# FlyballETS-PWR.net
KiCad netlist of a schematic drawn in EAGLE
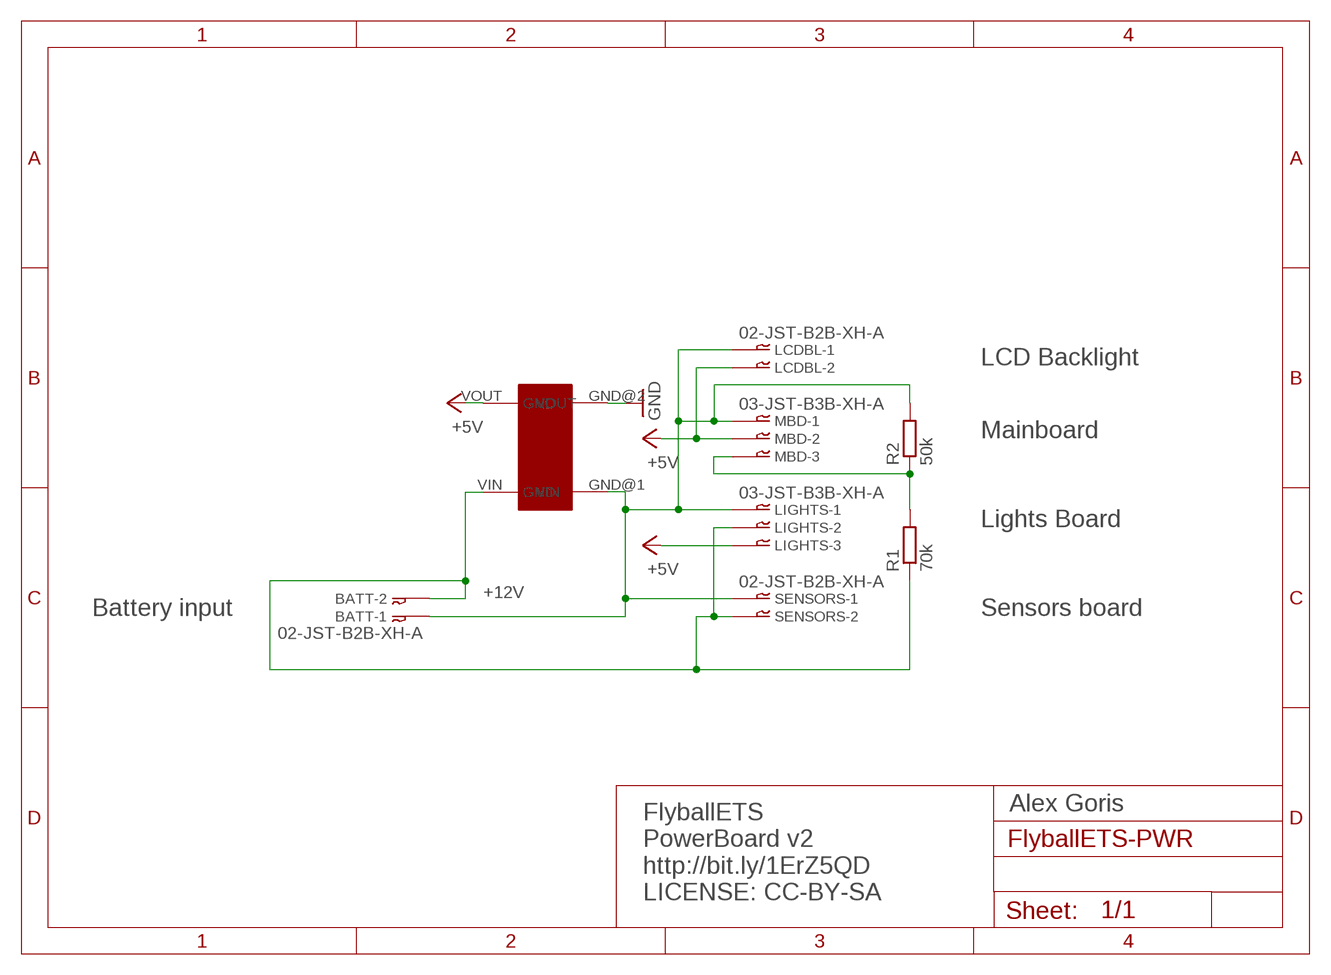
[diagram p0: schematic, sheet 1]

(export (version "E")
  (design (tool "Eeschema 10.0.6"))
  (components
    (comp (ref "BATT")
      (value "02-JST-B2B-XH-A")
      (footprint "eagle-import:B2B-XH")
      (libsource (lib "eagle-import") (part "02-JST-B2B-XH-A"))
    )
    (comp (ref "LCDBL")
      (value "02-JST-B2B-XH-A")
      (footprint "eagle-import:B2B-XH")
      (libsource (lib "eagle-import") (part "02-JST-B2B-XH-A"))
    )
    (comp (ref "LIGHTS")
      (value "03-JST-B3B-XH-A")
      (footprint "eagle-import:B3B-XH")
      (libsource (lib "eagle-import") (part "03-JST-B3B-XH-A"))
    )
    (comp (ref "MBD")
      (value "03-JST-B3B-XH-A")
      (footprint "eagle-import:B3B-XH")
      (libsource (lib "eagle-import") (part "03-JST-B3B-XH-A"))
    )
    (comp (ref "R1")
      (value "70k")
      (footprint "eagle-import:0207_10")
      (libsource (lib "eagle-import") (part "R-EU_0207/10"))
    )
    (comp (ref "R2")
      (value "50k")
      (footprint "eagle-import:0207_10")
      (libsource (lib "eagle-import") (part "R-EU_0207/10"))
    )
    (comp (ref "SENSORS")
      (value "02-JST-B2B-XH-A")
      (footprint "eagle-import:B2B-XH")
      (libsource (lib "eagle-import") (part "02-JST-B2B-XH-A"))
    )
    (comp (ref "U$1")
      (value "LM2596-BOARD")
      (footprint "eagle-import:LM2596-BOARD")
      (libsource (lib "eagle-import") (part "LM2596-BOARD"))
    )
  )
  (nets
    (net (code "1") (name "+5V") (class "Default")
      (node (ref "LCDBL") (pin "P$2") (pinfunction "1_P$2") (pintype "passive"))
      (node (ref "LIGHTS") (pin "P$3") (pinfunction "1_P$3") (pintype "passive"))
      (node (ref "MBD") (pin "P$2") (pinfunction "1_P$2") (pintype "passive"))
      (node (ref "U$1") (pin "VOUT") (pinfunction "VOUT_VOUT") (pintype "bidirectional"))
    )
    (net (code "2") (name "/+12V") (class "Default")
      (node (ref "BATT") (pin "P$2") (pinfunction "1_P$2") (pintype "passive"))
      (node (ref "LIGHTS") (pin "P$2") (pinfunction "1_P$2") (pintype "passive"))
      (node (ref "R1") (pin "1") (pinfunction "1_1") (pintype "passive"))
      (node (ref "SENSORS") (pin "P$2") (pinfunction "1_P$2") (pintype "passive"))
      (node (ref "U$1") (pin "VIN") (pinfunction "VIN_VIN") (pintype "bidirectional"))
    )
    (net (code "3") (name "GND") (class "Default")
      (node (ref "BATT") (pin "P$1") (pinfunction "1_P$1") (pintype "passive"))
      (node (ref "LCDBL") (pin "P$1") (pinfunction "1_P$1") (pintype "passive"))
      (node (ref "LIGHTS") (pin "P$1") (pinfunction "1_P$1") (pintype "passive"))
      (node (ref "MBD") (pin "P$1") (pinfunction "1_P$1") (pintype "passive"))
      (node (ref "R2") (pin "2") (pinfunction "2_2") (pintype "passive"))
      (node (ref "SENSORS") (pin "P$1") (pinfunction "1_P$1") (pintype "passive"))
      (node (ref "U$1") (pin "GND@1") (pinfunction "GND_GND@1") (pintype "bidirectional"))
      (node (ref "U$1") (pin "GND@2") (pinfunction "GND_GND@2") (pintype "bidirectional"))
    )
    (net (code "4") (name "Net-(MBDC-1)") (class "Default")
      (node (ref "MBD") (pin "P$3") (pinfunction "1_P$3") (pintype "passive"))
      (node (ref "R1") (pin "2") (pinfunction "2_2") (pintype "passive"))
      (node (ref "R2") (pin "1") (pinfunction "1_1") (pintype "passive"))
    )
  )
)
